# smile.net
KiCad netlist of a schematic drawn in EAGLE
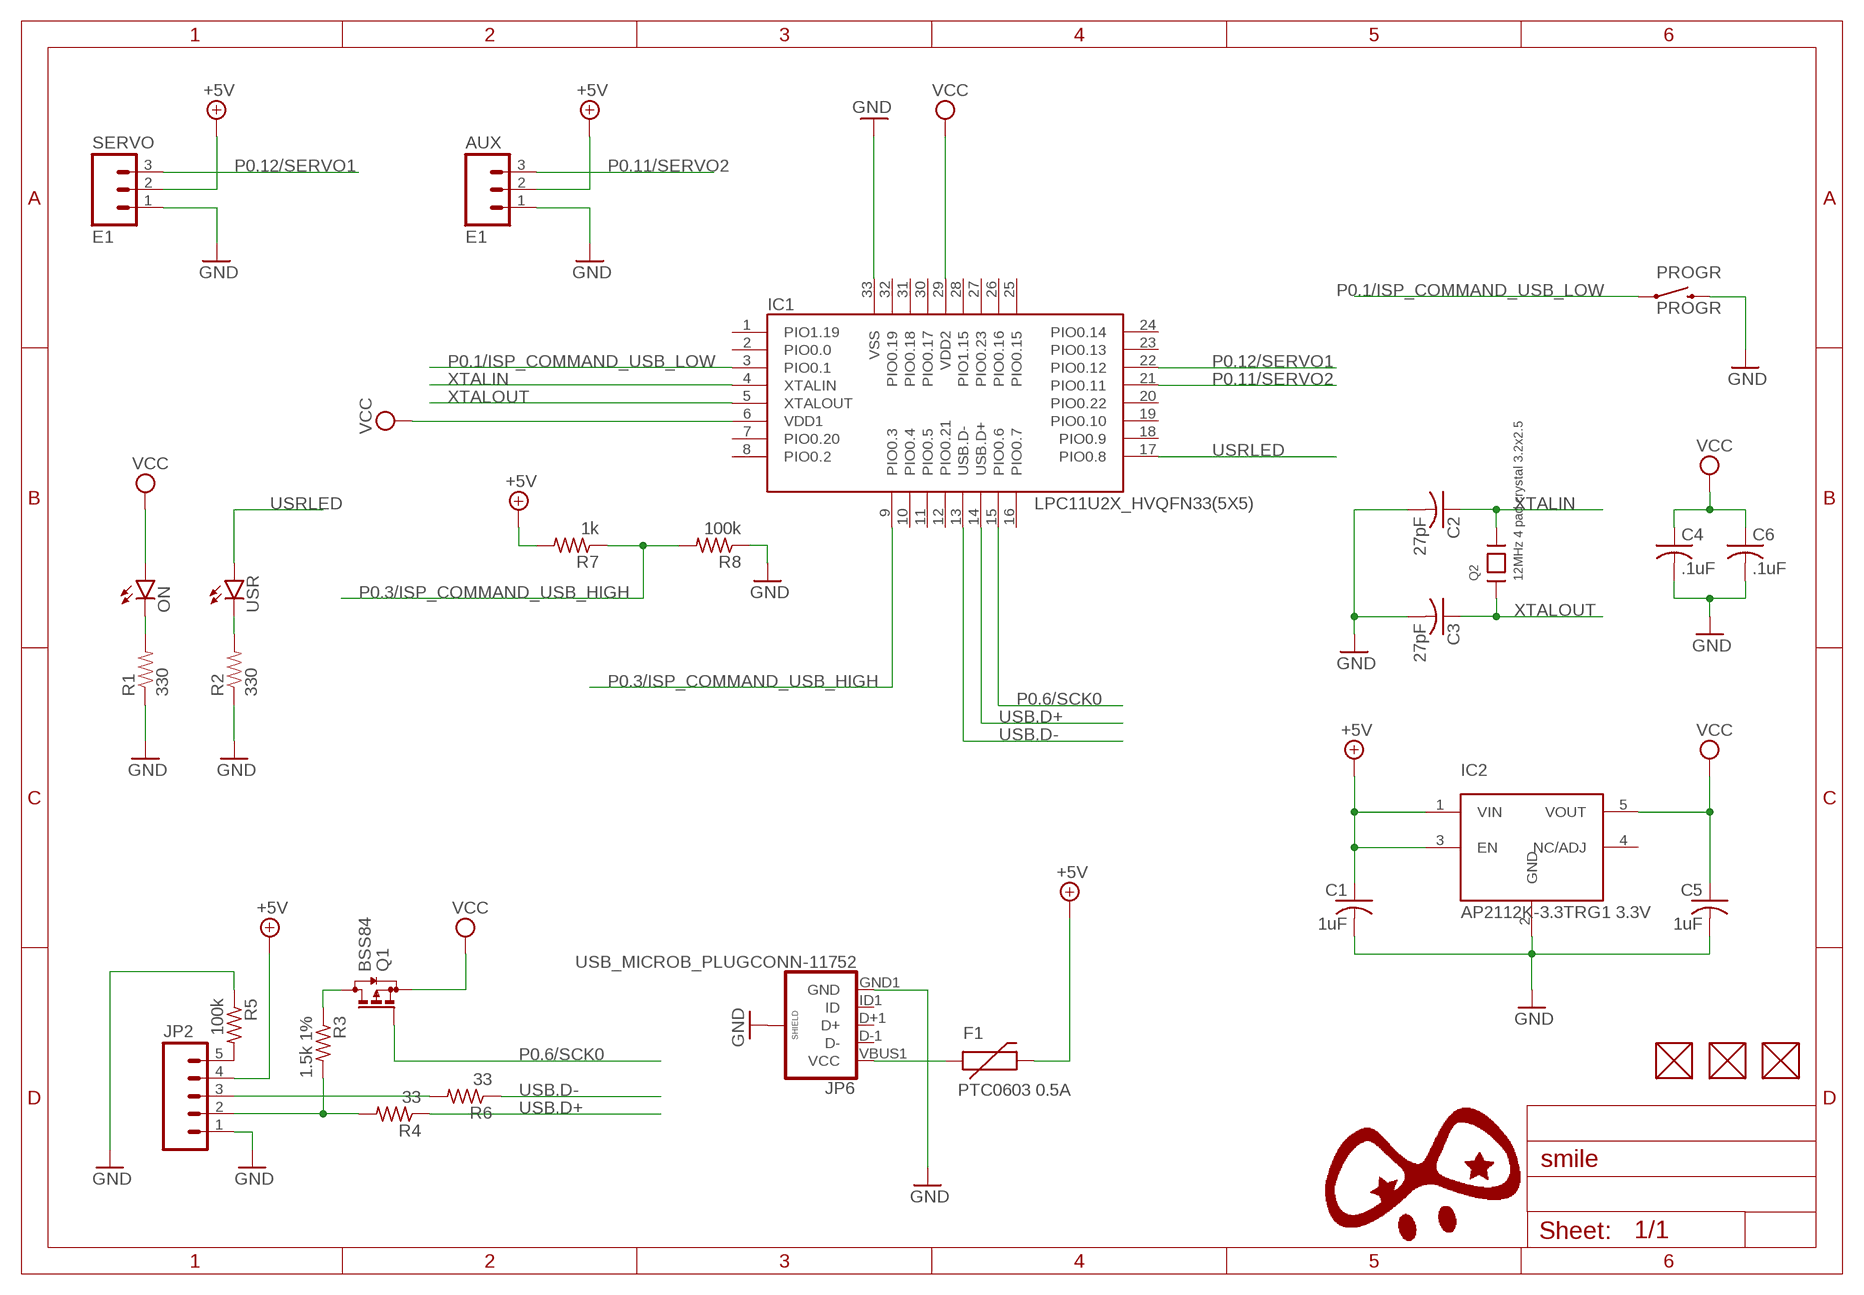
[diagram p0: schematic, sheet 1]

(export (version "E")
  (design (tool "Eeschema 10.0.6"))
  (components
    (comp (ref "AUX")
      (value "E1")
      (footprint "eagle-import:1X03_NO_SILK")
      (libsource (lib "eagle-import") (part "M031X03_NO_SILK"))
    )
    (comp (ref "C1")
      (value "1uF")
      (footprint "eagle-import:C0603K")
      (libsource (lib "eagle-import") (part "C-USC0603K"))
    )
    (comp (ref "C2")
      (value "27pF")
      (footprint "eagle-import:C0402K")
      (libsource (lib "eagle-import") (part "C-USC0402K"))
    )
    (comp (ref "C3")
      (value "27pF")
      (footprint "eagle-import:C0402K")
      (libsource (lib "eagle-import") (part "C-USC0402K"))
    )
    (comp (ref "C4")
      (value ".1uF")
      (footprint "eagle-import:C0402K")
      (libsource (lib "eagle-import") (part "C-USC0402K"))
    )
    (comp (ref "C5")
      (value "1uF")
      (footprint "eagle-import:C0603K")
      (libsource (lib "eagle-import") (part "C-USC0603K"))
    )
    (comp (ref "C6")
      (value ".1uF")
      (footprint "eagle-import:C0402K")
      (libsource (lib "eagle-import") (part "C-USC0402K"))
    )
    (comp (ref "F1")
      (value "PTC0603 0.5A")
      (footprint "eagle-import:0603")
      (libsource (lib "eagle-import") (part "PTC0603"))
    )
    (comp (ref "FUD1")
      (value "FIDUCIAL")
      (footprint "eagle-import:FIDUCIAL_40MIL")
      (libsource (lib "eagle-import") (part "FIDUCIAL"))
    )
    (comp (ref "FUD2")
      (value "FIDUCIAL")
      (footprint "eagle-import:FIDUCIAL_40MIL")
      (libsource (lib "eagle-import") (part "FIDUCIAL"))
    )
    (comp (ref "FUD3")
      (value "FIDUCIAL")
      (footprint "eagle-import:FIDUCIAL_40MIL")
      (libsource (lib "eagle-import") (part "FIDUCIAL"))
    )
    (comp (ref "IC1")
      (value "LPC11U2X_HVQFN33(5X5)")
      (footprint "eagle-import:HVQFN33_5X5MM")
      (libsource (lib "eagle-import") (part "LPC11U2X_HVQFN33(5X5)"))
    )
    (comp (ref "IC2")
      (value "AP2112K-3.3TRG1 3.3V")
      (footprint "eagle-import:SOT23-5")
      (libsource (lib "eagle-import") (part "5PIN_REG"))
    )
    (comp (ref "JP2")
      (value "M05LOCK")
      (footprint "eagle-import:1X05_LOCK")
      (libsource (lib "eagle-import") (part "M05LOCK"))
    )
    (comp (ref "JP6")
      (value "USB_MICROB_PLUGCONN-11752")
      (footprint "eagle-import:USB-B-MICRO-SMD_V03")
      (libsource (lib "eagle-import") (part "USB_MICROB_PLUGCONN-11752"))
    )
    (comp (ref "ON")
      (value "LED0603")
      (footprint "eagle-import:LED-0603")
      (libsource (lib "eagle-import") (part "LED0603"))
    )
    (comp (ref "PROGR")
      (value "PROGR")
      (footprint "eagle-import:TACTILE-PTH-SIDEEZ")
      (libsource (lib "eagle-import") (part "SWITCH-MOMENTARY-2SIDE_EZ"))
    )
    (comp (ref "Q1")
      (value "BSS84")
      (footprint "eagle-import:SOT23")
      (libsource (lib "eagle-import") (part "BSS84"))
    )
    (comp (ref "Q2")
      (value "12MHz 4 pad crystal 3.2x2.5")
      (footprint "eagle-import:CRYSTAL_3.2X2.5")
      (libsource (lib "eagle-import") (part "CRYSTAL3.2X2.5"))
    )
    (comp (ref "R1")
      (value "330")
      (footprint "eagle-import:0402-RES")
      (libsource (lib "eagle-import") (part "RESISTOR0402-RES"))
    )
    (comp (ref "R2")
      (value "330")
      (footprint "eagle-import:0402-RES")
      (libsource (lib "eagle-import") (part "RESISTOR0402-RES"))
    )
    (comp (ref "R3")
      (value "1.5k 1%")
      (footprint "eagle-import:R0402")
      (libsource (lib "eagle-import") (part "R-US_R0402"))
    )
    (comp (ref "R4")
      (value "33")
      (footprint "eagle-import:R0402")
      (libsource (lib "eagle-import") (part "R-US_R0402"))
    )
    (comp (ref "R5")
      (value "100k")
      (footprint "eagle-import:R0402")
      (libsource (lib "eagle-import") (part "R-US_R0402"))
    )
    (comp (ref "R6")
      (value "33")
      (footprint "eagle-import:R0402")
      (libsource (lib "eagle-import") (part "R-US_R0402"))
    )
    (comp (ref "R7")
      (value "1k")
      (footprint "eagle-import:R0402")
      (libsource (lib "eagle-import") (part "R-US_R0402"))
    )
    (comp (ref "R8")
      (value "100k")
      (footprint "eagle-import:R0402")
      (libsource (lib "eagle-import") (part "R-US_R0402"))
    )
    (comp (ref "SERVO")
      (value "E1")
      (footprint "eagle-import:1X03_NO_SILK")
      (libsource (lib "eagle-import") (part "M031X03_NO_SILK"))
    )
    (comp (ref "USR")
      (value "LED0603")
      (footprint "eagle-import:LED-0603")
      (libsource (lib "eagle-import") (part "LED0603"))
    )
  )
  (nets
    (net (code "1") (name "+5V") (class "Default")
      (node (ref "AUX") (pin "2") (pinfunction "2_2") (pintype "passive"))
      (node (ref "C1") (pin "1") (pinfunction "1_1") (pintype "passive"))
      (node (ref "F1") (pin "2") (pinfunction "2_2") (pintype "bidirectional"))
      (node (ref "IC2") (pin "1") (pinfunction "VIN_1") (pintype "bidirectional"))
      (node (ref "IC2") (pin "3") (pinfunction "EN_3") (pintype "bidirectional"))
      (node (ref "JP2") (pin "4") (pinfunction "4_4") (pintype "passive"))
      (node (ref "R7") (pin "2") (pinfunction "2_2") (pintype "passive"))
      (node (ref "SERVO") (pin "2") (pinfunction "2_2") (pintype "passive"))
    )
    (net (code "2") (name "/P0.1{slash}ISP_COMMAND_USB_LOW") (class "Default")
      (node (ref "IC1") (pin "3") (pinfunction "PIO0.1_3") (pintype "bidirectional"))
      (node (ref "PROGR") (pin "1") (pinfunction "1_1") (pintype "passive"))
    )
    (net (code "3") (name "/P0.3{slash}ISP_COMMAND_USB_HIGH") (class "Default")
      (node (ref "IC1") (pin "9") (pinfunction "PIO0.3_9") (pintype "bidirectional"))
      (node (ref "R7") (pin "1") (pinfunction "1_1") (pintype "passive"))
      (node (ref "R8") (pin "2") (pinfunction "2_2") (pintype "passive"))
    )
    (net (code "4") (name "/P0.6{slash}SCK0") (class "Default")
      (node (ref "IC1") (pin "15") (pinfunction "PIO0.6_15") (pintype "bidirectional"))
      (node (ref "Q1") (pin "1") (pinfunction "G_1") (pintype "passive"))
    )
    (net (code "5") (name "/P0.11{slash}SERVO2") (class "Default")
      (node (ref "AUX") (pin "3") (pinfunction "3_3") (pintype "passive"))
      (node (ref "IC1") (pin "21") (pinfunction "PIO0.11_21") (pintype "bidirectional"))
    )
    (net (code "6") (name "/P0.12{slash}SERVO1") (class "Default")
      (node (ref "IC1") (pin "22") (pinfunction "PIO0.12_22") (pintype "bidirectional"))
      (node (ref "SERVO") (pin "3") (pinfunction "3_3") (pintype "passive"))
    )
    (net (code "7") (name "/USB.D+") (class "Default")
      (node (ref "IC1") (pin "14") (pinfunction "USB.D+_14") (pintype "bidirectional"))
      (node (ref "R4") (pin "1") (pinfunction "1_1") (pintype "passive"))
    )
    (net (code "8") (name "/USB.D-") (class "Default")
      (node (ref "IC1") (pin "13") (pinfunction "USB.D-_13") (pintype "bidirectional"))
      (node (ref "R6") (pin "1") (pinfunction "1_1") (pintype "passive"))
    )
    (net (code "9") (name "/USRLED") (class "Default")
      (node (ref "IC1") (pin "17") (pinfunction "PIO0.8_17") (pintype "bidirectional"))
      (node (ref "USR") (pin "A") (pinfunction "A_A") (pintype "passive"))
    )
    (net (code "10") (name "/XTALIN") (class "Default")
      (node (ref "C2") (pin "1") (pinfunction "1_1") (pintype "passive"))
      (node (ref "IC1") (pin "4") (pinfunction "XTALIN_4") (pintype "bidirectional"))
      (node (ref "Q2") (pin "3") (pinfunction "P$2_3") (pintype "passive"))
    )
    (net (code "11") (name "/XTALOUT") (class "Default")
      (node (ref "C3") (pin "1") (pinfunction "1_1") (pintype "passive"))
      (node (ref "IC1") (pin "5") (pinfunction "XTALOUT_5") (pintype "bidirectional"))
      (node (ref "Q2") (pin "1") (pinfunction "P$1_1") (pintype "passive"))
    )
    (net (code "12") (name "GND") (class "Default")
      (node (ref "AUX") (pin "1") (pinfunction "1_1") (pintype "passive"))
      (node (ref "C1") (pin "2") (pinfunction "2_2") (pintype "passive"))
      (node (ref "C2") (pin "2") (pinfunction "2_2") (pintype "passive"))
      (node (ref "C3") (pin "2") (pinfunction "2_2") (pintype "passive"))
      (node (ref "C4") (pin "2") (pinfunction "2_2") (pintype "passive"))
      (node (ref "C5") (pin "2") (pinfunction "2_2") (pintype "passive"))
      (node (ref "C6") (pin "2") (pinfunction "2_2") (pintype "passive"))
      (node (ref "IC1") (pin "33") (pinfunction "VSS_33") (pintype "bidirectional"))
      (node (ref "IC2") (pin "2") (pinfunction "GND_2") (pintype "bidirectional"))
      (node (ref "JP2") (pin "1") (pinfunction "1_1") (pintype "passive"))
      (node (ref "JP6") (pin "GND1") (pinfunction "GND_GND1") (pintype "bidirectional"))
      (node (ref "JP6") (pin "SHIELD1") (pinfunction "SHIELD_SHIELD1") (pintype "bidirectional"))
      (node (ref "JP6") (pin "SHIELD2") (pinfunction "SHIELD_SHIELD2") (pintype "bidirectional"))
      (node (ref "JP6") (pin "SHIELD3") (pinfunction "SHIELD_SHIELD3") (pintype "bidirectional"))
      (node (ref "PROGR") (pin "2") (pinfunction "2_2") (pintype "passive"))
      (node (ref "R1") (pin "1") (pinfunction "1_1") (pintype "passive"))
      (node (ref "R2") (pin "1") (pinfunction "1_1") (pintype "passive"))
      (node (ref "R5") (pin "1") (pinfunction "1_1") (pintype "passive"))
      (node (ref "R8") (pin "1") (pinfunction "1_1") (pintype "passive"))
      (node (ref "SERVO") (pin "1") (pinfunction "1_1") (pintype "passive"))
    )
    (net (code "13") (name "Net-(JP2-Pad2)") (class "Default")
      (node (ref "JP2") (pin "2") (pinfunction "2_2") (pintype "passive"))
      (node (ref "R3") (pin "2") (pinfunction "2_2") (pintype "passive"))
      (node (ref "R4") (pin "2") (pinfunction "2_2") (pintype "passive"))
    )
    (net (code "14") (name "Net-(JP2-Pad3)") (class "Default")
      (node (ref "JP2") (pin "3") (pinfunction "3_3") (pintype "passive"))
      (node (ref "R6") (pin "2") (pinfunction "2_2") (pintype "passive"))
    )
    (net (code "15") (name "Net-(JP2-Pad5)") (class "Default")
      (node (ref "JP2") (pin "5") (pinfunction "5_5") (pintype "passive"))
      (node (ref "R5") (pin "2") (pinfunction "2_2") (pintype "passive"))
    )
    (net (code "16") (name "Net-(JP6-VCC)") (class "Default")
      (node (ref "F1") (pin "1") (pinfunction "1_1") (pintype "bidirectional"))
      (node (ref "JP6") (pin "VBUS1") (pinfunction "VCC_VBUS1") (pintype "bidirectional"))
    )
    (net (code "17") (name "Net-(ON-PadC)") (class "Default")
      (node (ref "ON") (pin "C") (pinfunction "C_C") (pintype "passive"))
      (node (ref "R1") (pin "2") (pinfunction "2_2") (pintype "passive"))
    )
    (net (code "18") (name "Net-(Q1-D)") (class "Default")
      (node (ref "Q1") (pin "3") (pinfunction "D_3") (pintype "passive"))
      (node (ref "R3") (pin "1") (pinfunction "1_1") (pintype "passive"))
    )
    (net (code "19") (name "Net-(R2-Pad2)") (class "Default")
      (node (ref "R2") (pin "2") (pinfunction "2_2") (pintype "passive"))
      (node (ref "USR") (pin "C") (pinfunction "C_C") (pintype "passive"))
    )
    (net (code "20") (name "VCC") (class "Default")
      (node (ref "C4") (pin "1") (pinfunction "1_1") (pintype "passive"))
      (node (ref "C5") (pin "1") (pinfunction "1_1") (pintype "passive"))
      (node (ref "C6") (pin "1") (pinfunction "1_1") (pintype "passive"))
      (node (ref "IC1") (pin "29") (pinfunction "VDD2_29") (pintype "bidirectional"))
      (node (ref "IC1") (pin "6") (pinfunction "VDD1_6") (pintype "bidirectional"))
      (node (ref "IC2") (pin "5") (pinfunction "VOUT_5") (pintype "bidirectional"))
      (node (ref "ON") (pin "A") (pinfunction "A_A") (pintype "passive"))
      (node (ref "Q1") (pin "2") (pinfunction "S_2") (pintype "passive"))
    )
    (net (code "21") (name "unconnected-(FUD1-PadP$1)") (class "Default")
      (node (ref "FUD1") (pin "P$1") (pinfunction "P$1_P$1") (pintype "no_connect"))
    )
    (net (code "22") (name "unconnected-(FUD2-PadP$1)") (class "Default")
      (node (ref "FUD2") (pin "P$1") (pinfunction "P$1_P$1") (pintype "no_connect"))
    )
    (net (code "23") (name "unconnected-(FUD3-PadP$1)") (class "Default")
      (node (ref "FUD3") (pin "P$1") (pinfunction "P$1_P$1") (pintype "no_connect"))
    )
    (net (code "24") (name "unconnected-(IC1-PIO0.0-Pad2)") (class "Default")
      (node (ref "IC1") (pin "2") (pinfunction "PIO0.0_2") (pintype "bidirectional"))
    )
    (net (code "25") (name "unconnected-(IC1-PIO0.2-Pad8)") (class "Default")
      (node (ref "IC1") (pin "8") (pinfunction "PIO0.2_8") (pintype "bidirectional"))
    )
    (net (code "26") (name "unconnected-(IC1-PIO0.4-Pad10)") (class "Default")
      (node (ref "IC1") (pin "10") (pinfunction "PIO0.4_10") (pintype "bidirectional"))
    )
    (net (code "27") (name "unconnected-(IC1-PIO0.5-Pad11)") (class "Default")
      (node (ref "IC1") (pin "11") (pinfunction "PIO0.5_11") (pintype "bidirectional"))
    )
    (net (code "28") (name "unconnected-(IC1-PIO0.7-Pad16)") (class "Default")
      (node (ref "IC1") (pin "16") (pinfunction "PIO0.7_16") (pintype "bidirectional"))
    )
    (net (code "29") (name "unconnected-(IC1-PIO0.9-Pad18)") (class "Default")
      (node (ref "IC1") (pin "18") (pinfunction "PIO0.9_18") (pintype "bidirectional"))
    )
    (net (code "30") (name "unconnected-(IC1-PIO0.10-Pad19)") (class "Default")
      (node (ref "IC1") (pin "19") (pinfunction "PIO0.10_19") (pintype "bidirectional"))
    )
    (net (code "31") (name "unconnected-(IC1-PIO0.13-Pad23)") (class "Default")
      (node (ref "IC1") (pin "23") (pinfunction "PIO0.13_23") (pintype "bidirectional"))
    )
    (net (code "32") (name "unconnected-(IC1-PIO0.14-Pad24)") (class "Default")
      (node (ref "IC1") (pin "24") (pinfunction "PIO0.14_24") (pintype "bidirectional"))
    )
    (net (code "33") (name "unconnected-(IC1-PIO0.15-Pad25)") (class "Default")
      (node (ref "IC1") (pin "25") (pinfunction "PIO0.15_25") (pintype "bidirectional"))
    )
    (net (code "34") (name "unconnected-(IC1-PIO0.16-Pad26)") (class "Default")
      (node (ref "IC1") (pin "26") (pinfunction "PIO0.16_26") (pintype "bidirectional"))
    )
    (net (code "35") (name "unconnected-(IC1-PIO0.17-Pad30)") (class "Default")
      (node (ref "IC1") (pin "30") (pinfunction "PIO0.17_30") (pintype "bidirectional"))
    )
    (net (code "36") (name "unconnected-(IC1-PIO0.18-Pad31)") (class "Default")
      (node (ref "IC1") (pin "31") (pinfunction "PIO0.18_31") (pintype "bidirectional"))
    )
    (net (code "37") (name "unconnected-(IC1-PIO0.19-Pad32)") (class "Default")
      (node (ref "IC1") (pin "32") (pinfunction "PIO0.19_32") (pintype "bidirectional"))
    )
    (net (code "38") (name "unconnected-(IC1-PIO0.20-Pad7)") (class "Default")
      (node (ref "IC1") (pin "7") (pinfunction "PIO0.20_7") (pintype "bidirectional"))
    )
    (net (code "39") (name "unconnected-(IC1-PIO0.21-Pad12)") (class "Default")
      (node (ref "IC1") (pin "12") (pinfunction "PIO0.21_12") (pintype "bidirectional"))
    )
    (net (code "40") (name "unconnected-(IC1-PIO0.22-Pad20)") (class "Default")
      (node (ref "IC1") (pin "20") (pinfunction "PIO0.22_20") (pintype "bidirectional"))
    )
    (net (code "41") (name "unconnected-(IC1-PIO0.23-Pad27)") (class "Default")
      (node (ref "IC1") (pin "27") (pinfunction "PIO0.23_27") (pintype "bidirectional"))
    )
    (net (code "42") (name "unconnected-(IC1-PIO1.15-Pad28)") (class "Default")
      (node (ref "IC1") (pin "28") (pinfunction "PIO1.15_28") (pintype "bidirectional"))
    )
    (net (code "43") (name "unconnected-(IC1-PIO1.19-Pad1)") (class "Default")
      (node (ref "IC1") (pin "1") (pinfunction "PIO1.19_1") (pintype "bidirectional"))
    )
    (net (code "44") (name "unconnected-(IC2-NC{slash}ADJ-Pad4)") (class "Default")
      (node (ref "IC2") (pin "4") (pinfunction "NC/ADJ_4") (pintype "bidirectional"))
    )
    (net (code "45") (name "unconnected-(JP6-D+-PadD+1)") (class "Default")
      (node (ref "JP6") (pin "D+1") (pinfunction "D+_D+1") (pintype "bidirectional"))
    )
    (net (code "46") (name "unconnected-(JP6-D--PadD-1)") (class "Default")
      (node (ref "JP6") (pin "D-1") (pinfunction "D-_D-1") (pintype "bidirectional"))
    )
    (net (code "47") (name "unconnected-(JP6-ID-PadID1)") (class "Default")
      (node (ref "JP6") (pin "ID1") (pinfunction "ID_ID1") (pintype "bidirectional"))
    )
  )
)
